# LEDs.net
KiCad netlist of a schematic drawn in Altium Designer
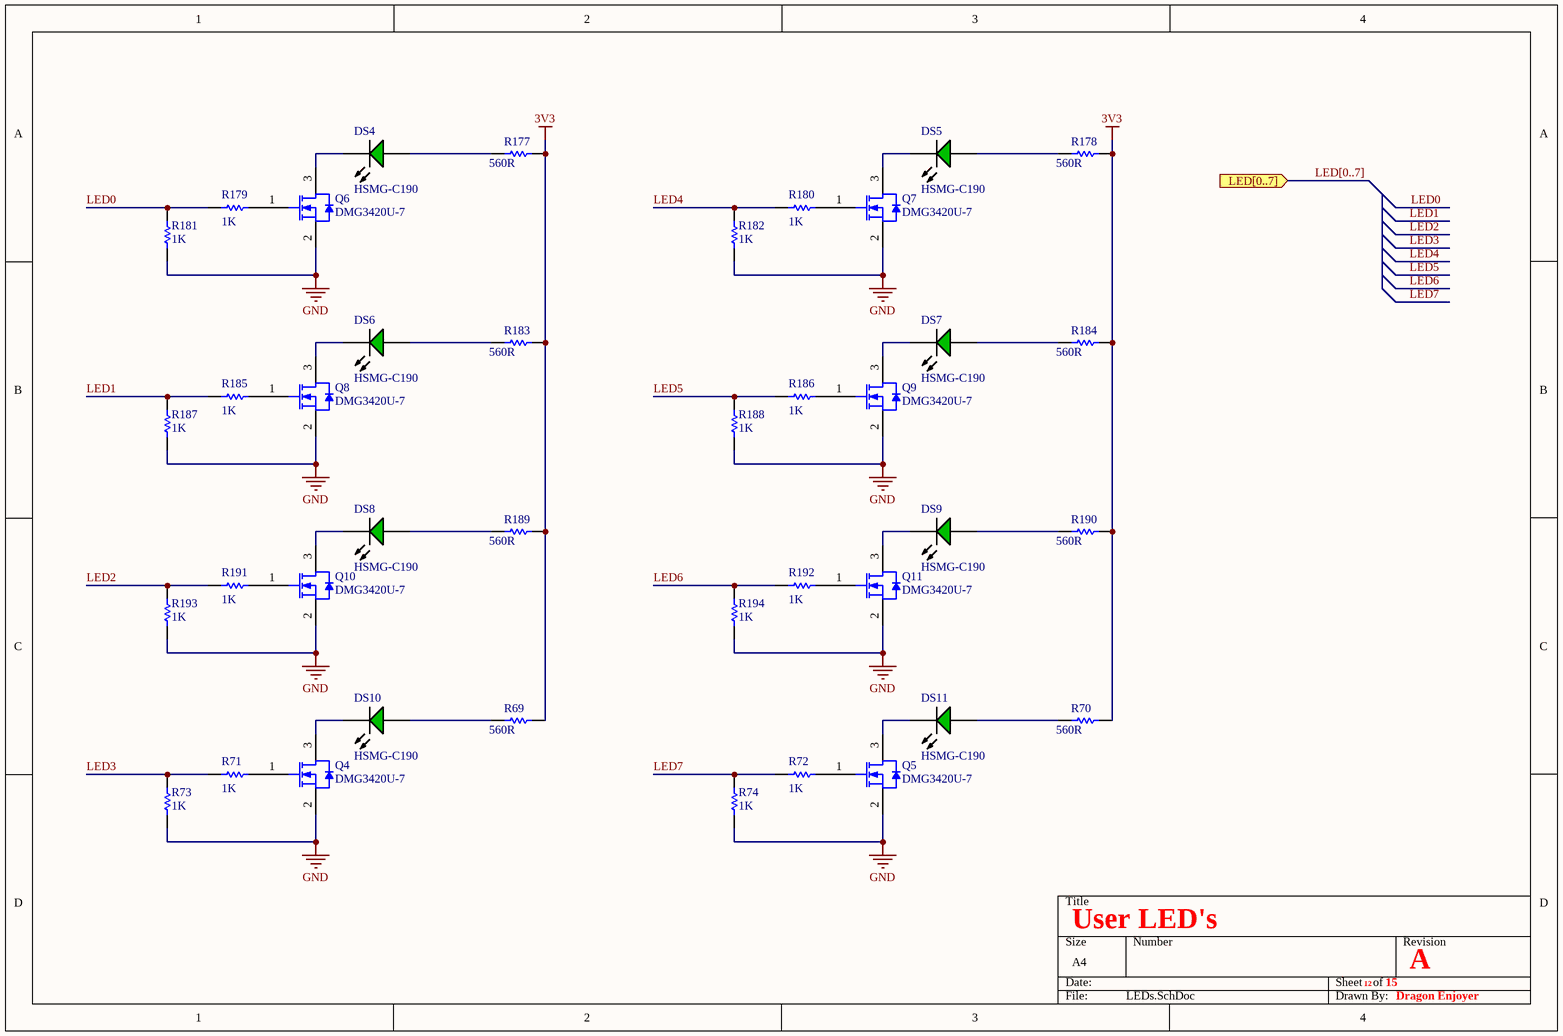
[diagram p0: LEDs.SchDoc]

(export (version "E")
  (design (tool "Eeschema 10.0.6"))
  (components
    (comp (ref "DS4")
      (value "HSMG-C190")
      (footprint "AVAG-HSMX-C190_V")
      (description "Chip LED, Green, 2.2 V, -40 to 85 degC, 2-Pin SMD, RoHS, Tape and Reel")
      (libsource (lib "Altium Content Vault") (part "LED-GREEN-AK-2"))
    )
    (comp (ref "DS5")
      (value "HSMG-C190")
      (footprint "AVAG-HSMX-C190_V")
      (description "Chip LED, Green, 2.2 V, -40 to 85 degC, 2-Pin SMD, RoHS, Tape and Reel")
      (libsource (lib "Altium Content Vault") (part "LED-GREEN-AK-2"))
    )
    (comp (ref "DS6")
      (value "HSMG-C190")
      (footprint "AVAG-HSMX-C190_V")
      (description "Chip LED, Green, 2.2 V, -40 to 85 degC, 2-Pin SMD, RoHS, Tape and Reel")
      (libsource (lib "Altium Content Vault") (part "LED-GREEN-AK-2"))
    )
    (comp (ref "DS7")
      (value "HSMG-C190")
      (footprint "AVAG-HSMX-C190_V")
      (description "Chip LED, Green, 2.2 V, -40 to 85 degC, 2-Pin SMD, RoHS, Tape and Reel")
      (libsource (lib "Altium Content Vault") (part "LED-GREEN-AK-2"))
    )
    (comp (ref "DS8")
      (value "HSMG-C190")
      (footprint "AVAG-HSMX-C190_V")
      (description "Chip LED, Green, 2.2 V, -40 to 85 degC, 2-Pin SMD, RoHS, Tape and Reel")
      (libsource (lib "Altium Content Vault") (part "LED-GREEN-AK-2"))
    )
    (comp (ref "DS9")
      (value "HSMG-C190")
      (footprint "AVAG-HSMX-C190_V")
      (description "Chip LED, Green, 2.2 V, -40 to 85 degC, 2-Pin SMD, RoHS, Tape and Reel")
      (libsource (lib "Altium Content Vault") (part "LED-GREEN-AK-2"))
    )
    (comp (ref "DS10")
      (value "HSMG-C190")
      (footprint "AVAG-HSMX-C190_V")
      (description "Chip LED, Green, 2.2 V, -40 to 85 degC, 2-Pin SMD, RoHS, Tape and Reel")
      (libsource (lib "Altium Content Vault") (part "LED-GREEN-AK-2"))
    )
    (comp (ref "DS11")
      (value "HSMG-C190")
      (footprint "AVAG-HSMX-C190_V")
      (description "Chip LED, Green, 2.2 V, -40 to 85 degC, 2-Pin SMD, RoHS, Tape and Reel")
      (libsource (lib "Altium Content Vault") (part "LED-GREEN-AK-2"))
    )
    (comp (ref "Q4")
      (value "DMG3420U-7")
      (footprint "DIOD-SOT23-3_B_V")
      (description "N-Channel Enhancement Mode MOSFET, 20 V, -55 to 150 degC, 3-Pin SOT23, RoHS, Tape and Reel")
      (fields (field (name "MANUFACTURER") "Diodes Inc"))
      (libsource (lib "Altium Content Vault") (part "NEMOS-GSD-3"))
    )
    (comp (ref "Q5")
      (value "DMG3420U-7")
      (footprint "DIOD-SOT23-3_B_V")
      (description "N-Channel Enhancement Mode MOSFET, 20 V, -55 to 150 degC, 3-Pin SOT23, RoHS, Tape and Reel")
      (fields (field (name "MANUFACTURER") "Diodes Inc"))
      (libsource (lib "Altium Content Vault") (part "NEMOS-GSD-3"))
    )
    (comp (ref "Q6")
      (value "DMG3420U-7")
      (footprint "DIOD-SOT23-3_B_V")
      (description "N-Channel Enhancement Mode MOSFET, 20 V, -55 to 150 degC, 3-Pin SOT23, RoHS, Tape and Reel")
      (fields (field (name "MANUFACTURER") "Diodes Inc"))
      (libsource (lib "Altium Content Vault") (part "NEMOS-GSD-3"))
    )
    (comp (ref "Q7")
      (value "DMG3420U-7")
      (footprint "DIOD-SOT23-3_B_V")
      (description "N-Channel Enhancement Mode MOSFET, 20 V, -55 to 150 degC, 3-Pin SOT23, RoHS, Tape and Reel")
      (fields (field (name "MANUFACTURER") "Diodes Inc"))
      (libsource (lib "Altium Content Vault") (part "NEMOS-GSD-3"))
    )
    (comp (ref "Q8")
      (value "DMG3420U-7")
      (footprint "DIOD-SOT23-3_B_V")
      (description "N-Channel Enhancement Mode MOSFET, 20 V, -55 to 150 degC, 3-Pin SOT23, RoHS, Tape and Reel")
      (fields (field (name "MANUFACTURER") "Diodes Inc"))
      (libsource (lib "Altium Content Vault") (part "NEMOS-GSD-3"))
    )
    (comp (ref "Q9")
      (value "DMG3420U-7")
      (footprint "DIOD-SOT23-3_B_V")
      (description "N-Channel Enhancement Mode MOSFET, 20 V, -55 to 150 degC, 3-Pin SOT23, RoHS, Tape and Reel")
      (fields (field (name "MANUFACTURER") "Diodes Inc"))
      (libsource (lib "Altium Content Vault") (part "NEMOS-GSD-3"))
    )
    (comp (ref "Q10")
      (value "DMG3420U-7")
      (footprint "DIOD-SOT23-3_B_V")
      (description "N-Channel Enhancement Mode MOSFET, 20 V, -55 to 150 degC, 3-Pin SOT23, RoHS, Tape and Reel")
      (fields (field (name "MANUFACTURER") "Diodes Inc"))
      (libsource (lib "Altium Content Vault") (part "NEMOS-GSD-3"))
    )
    (comp (ref "Q11")
      (value "DMG3420U-7")
      (footprint "DIOD-SOT23-3_B_V")
      (description "N-Channel Enhancement Mode MOSFET, 20 V, -55 to 150 degC, 3-Pin SOT23, RoHS, Tape and Reel")
      (fields (field (name "MANUFACTURER") "Diodes Inc"))
      (libsource (lib "Altium Content Vault") (part "NEMOS-GSD-3"))
    )
    (comp (ref "R69")
      (value "560R")
      (footprint "RESC1608X55X30LL20T20")
      (fields (field (name "PART NUMBER") "ERA3AEB561V") (field (name "MANUFACTURER") "Panasonic"))
      (libsource (lib "Altium Content Vault") (part "RES"))
    )
    (comp (ref "R70")
      (value "560R")
      (footprint "RESC1608X55X30LL20T20")
      (fields (field (name "PART NUMBER") "ERA3AEB561V") (field (name "MANUFACTURER") "Panasonic"))
      (libsource (lib "Altium Content Vault") (part "RES"))
    )
    (comp (ref "R71")
      (value "1K")
      (footprint "RESC1005X40X25NL05T10")
      (fields (field (name "PART NUMBER") "RC0402FR-071KL") (field (name "MANUFACTURER") "Yageo / Phycomp"))
      (libsource (lib "Altium Content Vault") (part "RES"))
    )
    (comp (ref "R72")
      (value "1K")
      (footprint "RESC1005X40X25NL05T10")
      (fields (field (name "PART NUMBER") "RC0402FR-071KL") (field (name "MANUFACTURER") "Yageo / Phycomp"))
      (libsource (lib "Altium Content Vault") (part "RES"))
    )
    (comp (ref "R73")
      (value "1K")
      (footprint "RESC1005X40X25NL05T10")
      (fields (field (name "PART NUMBER") "RC0402FR-071KL") (field (name "MANUFACTURER") "Yageo / Phycomp"))
      (libsource (lib "Altium Content Vault") (part "RES"))
    )
    (comp (ref "R74")
      (value "1K")
      (footprint "RESC1005X40X25NL05T10")
      (fields (field (name "PART NUMBER") "RC0402FR-071KL") (field (name "MANUFACTURER") "Yageo / Phycomp"))
      (libsource (lib "Altium Content Vault") (part "RES"))
    )
    (comp (ref "R177")
      (value "560R")
      (footprint "RESC1608X55X30LL20T20")
      (fields (field (name "PART NUMBER") "ERA3AEB561V") (field (name "MANUFACTURER") "Panasonic"))
      (libsource (lib "Altium Content Vault") (part "RES"))
    )
    (comp (ref "R178")
      (value "560R")
      (footprint "RESC1608X55X30LL20T20")
      (fields (field (name "PART NUMBER") "ERA3AEB561V") (field (name "MANUFACTURER") "Panasonic"))
      (libsource (lib "Altium Content Vault") (part "RES"))
    )
    (comp (ref "R179")
      (value "1K")
      (footprint "RESC1005X40X25NL05T10")
      (fields (field (name "PART NUMBER") "RC0402FR-071KL") (field (name "MANUFACTURER") "Yageo / Phycomp"))
      (libsource (lib "Altium Content Vault") (part "RES"))
    )
    (comp (ref "R180")
      (value "1K")
      (footprint "RESC1005X40X25NL05T10")
      (fields (field (name "PART NUMBER") "RC0402FR-071KL") (field (name "MANUFACTURER") "Yageo / Phycomp"))
      (libsource (lib "Altium Content Vault") (part "RES"))
    )
    (comp (ref "R181")
      (value "1K")
      (footprint "RESC1005X40X25NL05T10")
      (fields (field (name "PART NUMBER") "RC0402FR-071KL") (field (name "MANUFACTURER") "Yageo / Phycomp"))
      (libsource (lib "Altium Content Vault") (part "RES"))
    )
    (comp (ref "R182")
      (value "1K")
      (footprint "RESC1005X40X25NL05T10")
      (fields (field (name "PART NUMBER") "RC0402FR-071KL") (field (name "MANUFACTURER") "Yageo / Phycomp"))
      (libsource (lib "Altium Content Vault") (part "RES"))
    )
    (comp (ref "R183")
      (value "560R")
      (footprint "RESC1608X55X30LL20T20")
      (fields (field (name "PART NUMBER") "ERA3AEB561V") (field (name "MANUFACTURER") "Panasonic"))
      (libsource (lib "Altium Content Vault") (part "RES"))
    )
    (comp (ref "R184")
      (value "560R")
      (footprint "RESC1608X55X30LL20T20")
      (fields (field (name "PART NUMBER") "ERA3AEB561V") (field (name "MANUFACTURER") "Panasonic"))
      (libsource (lib "Altium Content Vault") (part "RES"))
    )
    (comp (ref "R185")
      (value "1K")
      (footprint "RESC1005X40X25NL05T10")
      (fields (field (name "PART NUMBER") "RC0402FR-071KL") (field (name "MANUFACTURER") "Yageo / Phycomp"))
      (libsource (lib "Altium Content Vault") (part "RES"))
    )
    (comp (ref "R186")
      (value "1K")
      (footprint "RESC1005X40X25NL05T10")
      (fields (field (name "PART NUMBER") "RC0402FR-071KL") (field (name "MANUFACTURER") "Yageo / Phycomp"))
      (libsource (lib "Altium Content Vault") (part "RES"))
    )
    (comp (ref "R187")
      (value "1K")
      (footprint "RESC1005X40X25NL05T10")
      (fields (field (name "PART NUMBER") "RC0402FR-071KL") (field (name "MANUFACTURER") "Yageo / Phycomp"))
      (libsource (lib "Altium Content Vault") (part "RES"))
    )
    (comp (ref "R188")
      (value "1K")
      (footprint "RESC1005X40X25NL05T10")
      (fields (field (name "PART NUMBER") "RC0402FR-071KL") (field (name "MANUFACTURER") "Yageo / Phycomp"))
      (libsource (lib "Altium Content Vault") (part "RES"))
    )
    (comp (ref "R189")
      (value "560R")
      (footprint "RESC1608X55X30LL20T20")
      (fields (field (name "PART NUMBER") "ERA3AEB561V") (field (name "MANUFACTURER") "Panasonic"))
      (libsource (lib "Altium Content Vault") (part "RES"))
    )
    (comp (ref "R190")
      (value "560R")
      (footprint "RESC1608X55X30LL20T20")
      (fields (field (name "PART NUMBER") "ERA3AEB561V") (field (name "MANUFACTURER") "Panasonic"))
      (libsource (lib "Altium Content Vault") (part "RES"))
    )
    (comp (ref "R191")
      (value "1K")
      (footprint "RESC1005X40X25NL05T10")
      (fields (field (name "PART NUMBER") "RC0402FR-071KL") (field (name "MANUFACTURER") "Yageo / Phycomp"))
      (libsource (lib "Altium Content Vault") (part "RES"))
    )
    (comp (ref "R192")
      (value "1K")
      (footprint "RESC1005X40X25NL05T10")
      (fields (field (name "PART NUMBER") "RC0402FR-071KL") (field (name "MANUFACTURER") "Yageo / Phycomp"))
      (libsource (lib "Altium Content Vault") (part "RES"))
    )
    (comp (ref "R193")
      (value "1K")
      (footprint "RESC1005X40X25NL05T10")
      (fields (field (name "PART NUMBER") "RC0402FR-071KL") (field (name "MANUFACTURER") "Yageo / Phycomp"))
      (libsource (lib "Altium Content Vault") (part "RES"))
    )
    (comp (ref "R194")
      (value "1K")
      (footprint "RESC1005X40X25NL05T10")
      (fields (field (name "PART NUMBER") "RC0402FR-071KL") (field (name "MANUFACTURER") "Yageo / Phycomp"))
      (libsource (lib "Altium Content Vault") (part "RES"))
    )
  )
  (nets
    (net (code "1") (name "/LED0") (class "Default")
      (node (ref "R179") (pin "1") (pinfunction "1_1") (pintype "passive"))
      (node (ref "R181") (pin "2") (pinfunction "2_2") (pintype "passive"))
    )
    (net (code "2") (name "/LED1") (class "Default")
      (node (ref "R185") (pin "1") (pinfunction "1_1") (pintype "passive"))
      (node (ref "R187") (pin "2") (pinfunction "2_2") (pintype "passive"))
    )
    (net (code "3") (name "/LED2") (class "Default")
      (node (ref "R191") (pin "1") (pinfunction "1_1") (pintype "passive"))
      (node (ref "R193") (pin "2") (pinfunction "2_2") (pintype "passive"))
    )
    (net (code "4") (name "/LED3") (class "Default")
      (node (ref "R71") (pin "1") (pinfunction "1_1") (pintype "passive"))
      (node (ref "R73") (pin "2") (pinfunction "2_2") (pintype "passive"))
    )
    (net (code "5") (name "/LED4") (class "Default")
      (node (ref "R180") (pin "1") (pinfunction "1_1") (pintype "passive"))
      (node (ref "R182") (pin "2") (pinfunction "2_2") (pintype "passive"))
    )
    (net (code "6") (name "/LED5") (class "Default")
      (node (ref "R186") (pin "1") (pinfunction "1_1") (pintype "passive"))
      (node (ref "R188") (pin "2") (pinfunction "2_2") (pintype "passive"))
    )
    (net (code "7") (name "/LED6") (class "Default")
      (node (ref "R192") (pin "1") (pinfunction "1_1") (pintype "passive"))
      (node (ref "R194") (pin "2") (pinfunction "2_2") (pintype "passive"))
    )
    (net (code "8") (name "/LED7") (class "Default")
      (node (ref "R72") (pin "1") (pinfunction "1_1") (pintype "passive"))
      (node (ref "R74") (pin "2") (pinfunction "2_2") (pintype "passive"))
    )
    (net (code "10") (name "3V3") (class "Default")
      (node (ref "R177") (pin "2") (pinfunction "2_2") (pintype "passive"))
      (node (ref "R178") (pin "2") (pinfunction "2_2") (pintype "passive"))
      (node (ref "R183") (pin "2") (pinfunction "2_2") (pintype "passive"))
      (node (ref "R184") (pin "2") (pinfunction "2_2") (pintype "passive"))
      (node (ref "R189") (pin "2") (pinfunction "2_2") (pintype "passive"))
      (node (ref "R190") (pin "2") (pinfunction "2_2") (pintype "passive"))
      (node (ref "R69") (pin "2") (pinfunction "2_2") (pintype "passive"))
      (node (ref "R70") (pin "2") (pinfunction "2_2") (pintype "passive"))
    )
    (net (code "11") (name "GND") (class "Default")
      (node (ref "Q10") (pin "2") (pinfunction "S_2") (pintype "passive"))
      (node (ref "Q11") (pin "2") (pinfunction "S_2") (pintype "passive"))
      (node (ref "Q4") (pin "2") (pinfunction "S_2") (pintype "passive"))
      (node (ref "Q5") (pin "2") (pinfunction "S_2") (pintype "passive"))
      (node (ref "Q6") (pin "2") (pinfunction "S_2") (pintype "passive"))
      (node (ref "Q7") (pin "2") (pinfunction "S_2") (pintype "passive"))
      (node (ref "Q8") (pin "2") (pinfunction "S_2") (pintype "passive"))
      (node (ref "Q9") (pin "2") (pinfunction "S_2") (pintype "passive"))
      (node (ref "R181") (pin "1") (pinfunction "1_1") (pintype "passive"))
      (node (ref "R182") (pin "1") (pinfunction "1_1") (pintype "passive"))
      (node (ref "R187") (pin "1") (pinfunction "1_1") (pintype "passive"))
      (node (ref "R188") (pin "1") (pinfunction "1_1") (pintype "passive"))
      (node (ref "R193") (pin "1") (pinfunction "1_1") (pintype "passive"))
      (node (ref "R194") (pin "1") (pinfunction "1_1") (pintype "passive"))
      (node (ref "R73") (pin "1") (pinfunction "1_1") (pintype "passive"))
      (node (ref "R74") (pin "1") (pinfunction "1_1") (pintype "passive"))
    )
    (net (code "12") (name "Net-(DS4-A)") (class "Default")
      (node (ref "DS4") (pin "1") (pinfunction "A_1") (pintype "passive"))
      (node (ref "R177") (pin "1") (pinfunction "1_1") (pintype "passive"))
    )
    (net (code "13") (name "Net-(DS4-K)") (class "Default")
      (node (ref "DS4") (pin "2") (pinfunction "K_2") (pintype "passive"))
      (node (ref "Q6") (pin "3") (pinfunction "D_3") (pintype "passive"))
    )
    (net (code "14") (name "Net-(DS5-A)") (class "Default")
      (node (ref "DS5") (pin "1") (pinfunction "A_1") (pintype "passive"))
      (node (ref "R178") (pin "1") (pinfunction "1_1") (pintype "passive"))
    )
    (net (code "15") (name "Net-(DS5-K)") (class "Default")
      (node (ref "DS5") (pin "2") (pinfunction "K_2") (pintype "passive"))
      (node (ref "Q7") (pin "3") (pinfunction "D_3") (pintype "passive"))
    )
    (net (code "16") (name "Net-(DS6-A)") (class "Default")
      (node (ref "DS6") (pin "1") (pinfunction "A_1") (pintype "passive"))
      (node (ref "R183") (pin "1") (pinfunction "1_1") (pintype "passive"))
    )
    (net (code "17") (name "Net-(DS6-K)") (class "Default")
      (node (ref "DS6") (pin "2") (pinfunction "K_2") (pintype "passive"))
      (node (ref "Q8") (pin "3") (pinfunction "D_3") (pintype "passive"))
    )
    (net (code "18") (name "Net-(DS7-A)") (class "Default")
      (node (ref "DS7") (pin "1") (pinfunction "A_1") (pintype "passive"))
      (node (ref "R184") (pin "1") (pinfunction "1_1") (pintype "passive"))
    )
    (net (code "19") (name "Net-(DS7-K)") (class "Default")
      (node (ref "DS7") (pin "2") (pinfunction "K_2") (pintype "passive"))
      (node (ref "Q9") (pin "3") (pinfunction "D_3") (pintype "passive"))
    )
    (net (code "20") (name "Net-(DS8-A)") (class "Default")
      (node (ref "DS8") (pin "1") (pinfunction "A_1") (pintype "passive"))
      (node (ref "R189") (pin "1") (pinfunction "1_1") (pintype "passive"))
    )
    (net (code "21") (name "Net-(DS8-K)") (class "Default")
      (node (ref "DS8") (pin "2") (pinfunction "K_2") (pintype "passive"))
      (node (ref "Q10") (pin "3") (pinfunction "D_3") (pintype "passive"))
    )
    (net (code "22") (name "Net-(DS9-A)") (class "Default")
      (node (ref "DS9") (pin "1") (pinfunction "A_1") (pintype "passive"))
      (node (ref "R190") (pin "1") (pinfunction "1_1") (pintype "passive"))
    )
    (net (code "23") (name "Net-(DS9-K)") (class "Default")
      (node (ref "DS9") (pin "2") (pinfunction "K_2") (pintype "passive"))
      (node (ref "Q11") (pin "3") (pinfunction "D_3") (pintype "passive"))
    )
    (net (code "24") (name "Net-(DS10-A)") (class "Default")
      (node (ref "DS10") (pin "1") (pinfunction "A_1") (pintype "passive"))
      (node (ref "R69") (pin "1") (pinfunction "1_1") (pintype "passive"))
    )
    (net (code "25") (name "Net-(DS10-K)") (class "Default")
      (node (ref "DS10") (pin "2") (pinfunction "K_2") (pintype "passive"))
      (node (ref "Q4") (pin "3") (pinfunction "D_3") (pintype "passive"))
    )
    (net (code "26") (name "Net-(DS11-A)") (class "Default")
      (node (ref "DS11") (pin "1") (pinfunction "A_1") (pintype "passive"))
      (node (ref "R70") (pin "1") (pinfunction "1_1") (pintype "passive"))
    )
    (net (code "27") (name "Net-(DS11-K)") (class "Default")
      (node (ref "DS11") (pin "2") (pinfunction "K_2") (pintype "passive"))
      (node (ref "Q5") (pin "3") (pinfunction "D_3") (pintype "passive"))
    )
    (net (code "28") (name "Net-(Q4-G)") (class "Default")
      (node (ref "Q4") (pin "1") (pinfunction "G_1") (pintype "passive"))
      (node (ref "R71") (pin "2") (pinfunction "2_2") (pintype "passive"))
    )
    (net (code "29") (name "Net-(Q5-G)") (class "Default")
      (node (ref "Q5") (pin "1") (pinfunction "G_1") (pintype "passive"))
      (node (ref "R72") (pin "2") (pinfunction "2_2") (pintype "passive"))
    )
    (net (code "30") (name "Net-(Q6-G)") (class "Default")
      (node (ref "Q6") (pin "1") (pinfunction "G_1") (pintype "passive"))
      (node (ref "R179") (pin "2") (pinfunction "2_2") (pintype "passive"))
    )
    (net (code "31") (name "Net-(Q7-G)") (class "Default")
      (node (ref "Q7") (pin "1") (pinfunction "G_1") (pintype "passive"))
      (node (ref "R180") (pin "2") (pinfunction "2_2") (pintype "passive"))
    )
    (net (code "32") (name "Net-(Q8-G)") (class "Default")
      (node (ref "Q8") (pin "1") (pinfunction "G_1") (pintype "passive"))
      (node (ref "R185") (pin "2") (pinfunction "2_2") (pintype "passive"))
    )
    (net (code "33") (name "Net-(Q9-G)") (class "Default")
      (node (ref "Q9") (pin "1") (pinfunction "G_1") (pintype "passive"))
      (node (ref "R186") (pin "2") (pinfunction "2_2") (pintype "passive"))
    )
    (net (code "34") (name "Net-(Q10-G)") (class "Default")
      (node (ref "Q10") (pin "1") (pinfunction "G_1") (pintype "passive"))
      (node (ref "R191") (pin "2") (pinfunction "2_2") (pintype "passive"))
    )
    (net (code "35") (name "Net-(Q11-G)") (class "Default")
      (node (ref "Q11") (pin "1") (pinfunction "G_1") (pintype "passive"))
      (node (ref "R192") (pin "2") (pinfunction "2_2") (pintype "passive"))
    )
  )
)
